# ProDocument_1_2024-06-25.net
KiCad netlist of a schematic drawn in EasyEDA Pro
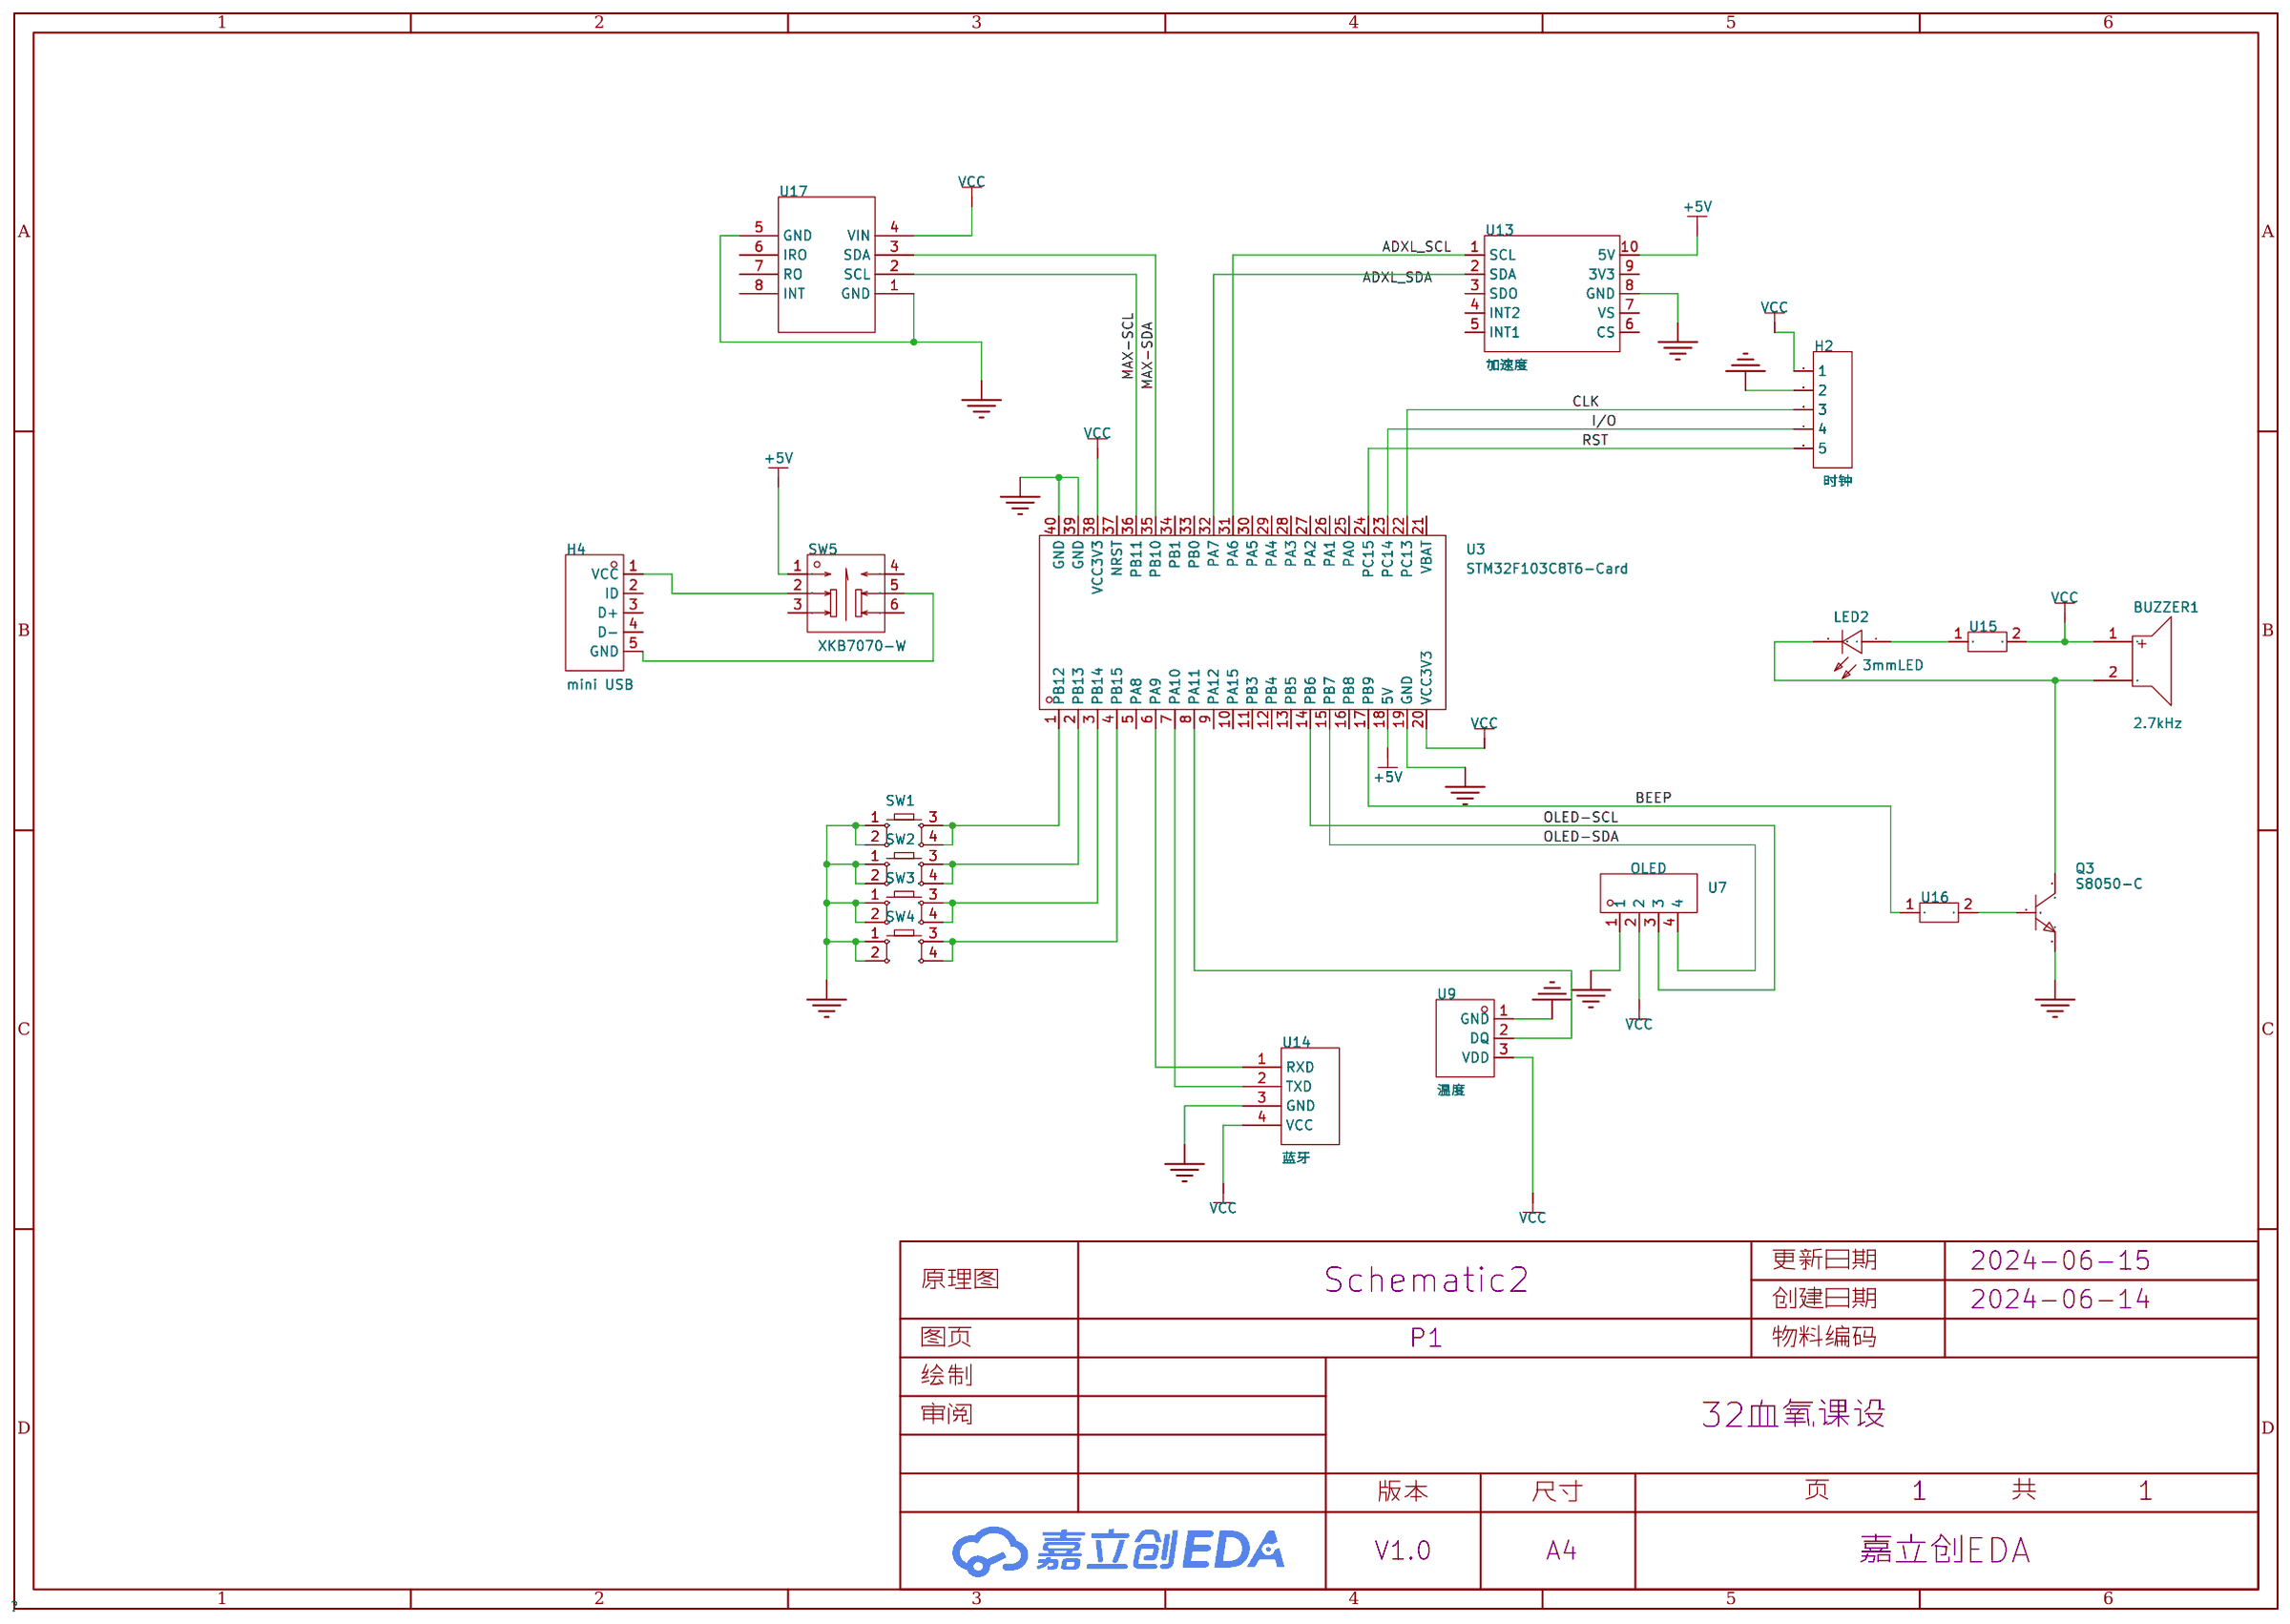
[diagram p0: schematic sheet]

(export (version "E")
  (design (tool "Eeschema 10.0.6"))
  (components
    (comp (ref "BUZZER1")
      (value "2.7kHz")
      (footprint "easyedapro:BUZ-TH_BD9.0-P4.00-D0.6-FD")
      (description "驱动方式:无源(外部驱动);构造类型:电磁式;频率:2.7kHz;声压(SPL):85dB@3V,10cm;")
      (fields (field (name "Manufacturer Part") "QMB-09B-03") (field (name "Manufacturer") "华能"))
      (libsource (lib "easyedapro") (part "QMB-09B-03"))
    )
    (comp (ref "H2")
      (value "时钟")
      (footprint "easyedapro:HDR-TH_5P-P2.54-V-F")
      (libsource (lib "easyedapro") (part "Header-Female-2.54_1x5"))
    )
    (comp (ref "H4") (value "mini USB") (libsource (lib "easyedapro") (part "mini USB")))
    (comp (ref "LED2")
      (value "3mmLED")
      (footprint "easyedapro:LED-TH_BD3.8-P2.54-FD")
      (fields
        (field (name "Manufacturer Part") "204-10SDRD/S530-A3-L")
        (field (name "Manufacturer") "EVERLIGHT(亿光)")
      )
      (libsource (lib "easyedapro") (part "3mmLED"))
    )
    (comp (ref "Q3")
      (value "S8050-C")
      (footprint "easyedapro:TO-92-3_L4.9-W3.7-P1.27-R")
      (description "晶体管类型:NPN;集电极电流(Ic):800mA;集射极击穿电压(Vceo):25V;功率(Pd):625mW;直流电流增益(hFE@Ic,Vce):120@100mA,1V;")
      (fields (field (name "Manufacturer") "BLUE ROCKET(蓝箭)"))
      (libsource (lib "easyedapro") (part "S8050-C"))
    )
    (comp (ref "SW1")
      (value "~")
      (footprint "easyedapro:SW-SMD_4P-L6.0-W6.0-P4.50-LS9.0-2")
      (libsource (lib "easyedapro") (part "轻触按键"))
    )
    (comp (ref "SW2")
      (value "~")
      (footprint "easyedapro:SW-SMD_4P-L6.0-W6.0-P4.50-LS9.0-2")
      (libsource (lib "easyedapro") (part "轻触按键"))
    )
    (comp (ref "SW3")
      (value "~")
      (footprint "easyedapro:SW-SMD_4P-L6.0-W6.0-P4.50-LS9.0-2")
      (libsource (lib "easyedapro") (part "轻触按键"))
    )
    (comp (ref "SW4")
      (value "~")
      (footprint "easyedapro:SW-SMD_4P-L6.0-W6.0-P4.50-LS9.0-2")
      (libsource (lib "easyedapro") (part "轻触按键"))
    )
    (comp (ref "SW5")
      (value "XKB7070-W")
      (footprint "easyedapro:SW-TH_6P-L7.2-W7.2-P2.00-LS5.0")
      (description "电路结构:-;自锁/无锁:无锁;安装方式:直插;触点电流:100mA;额定电压 (AC):250V;额定电压 (DC):30V;带灯:不带;作用力:160gf;机械寿命:1万次;")
      (fields (field (name "Manufacturer") "XKB Connectivity(中国星坤)"))
      (libsource (lib "easyedapro") (part "XKB7070-W"))
    )
    (comp (ref "U3")
      (value "STM32F103C8T6-Card")
      (footprint "easyedapro:CONN-TH_L53.3-W22.9_STM32F103C8T6-CARD")
      (libsource (lib "easyedapro") (part "STM32F103C8T6-CARD"))
    )
    (comp (ref "U7")
      (value "OLED")
      (footprint "easyedapro:OLED-TH12864")
      (libsource (lib "easyedapro") (part "1.3寸OLED显示屏12864"))
    )
    (comp (ref "U9")
      (value "温度")
      (footprint "easyedapro:TO-92-3_L4.9-W3.7-P1.27-L")
      (description "温度范围:-55°C~+125°C;精度:±0.4°C;接口类型:-;")
      (fields (field (name "Manufacturer Part") "DS18B20") (field (name "Manufacturer") "UMW(友台半导体)"))
      (libsource (lib "easyedapro") (part "DS18B20"))
    )
    (comp (ref "U13")
      (value "加速度")
      (footprint "easyedapro:HDR-TH_2x5P-P2.54-V-F-R2-C5-S2.54")
      (libsource (lib "easyedapro") (part "ADXL345"))
    )
    (comp (ref "U14")
      (value "蓝牙")
      (footprint "easyedapro:BT04-A")
      (libsource (lib "easyedapro") (part "BT04-A"))
    )
    (comp (ref "U15")
      (value "~")
      (footprint "easyedapro:R_AXIAL-0.3")
      (libsource (lib "easyedapro") (part "直插电阻"))
    )
    (comp (ref "U16")
      (value "~")
      (footprint "easyedapro:R_AXIAL-0.3")
      (libsource (lib "easyedapro") (part "直插电阻"))
    )
    (comp (ref "U17") (value "~") (libsource (lib "easyedapro") (part "MAX30102")))
  )
  (nets
    (net (code "1") (name "+5V") (class "Default")
      (node (ref "SW5") (pin "1") (pinfunction "1_1") (pintype "unspecified"))
      (node (ref "U13") (pin "10") (pinfunction "5V_10") (pintype "input"))
      (node (ref "U3") (pin "18") (pinfunction "5V_18") (pintype "unspecified"))
    )
    (net (code "2") (name "/ADXL_SCL") (class "Default")
      (node (ref "U13") (pin "1") (pinfunction "SCL_1") (pintype "input"))
      (node (ref "U3") (pin "31") (pinfunction "PA6_31") (pintype "unspecified"))
    )
    (net (code "3") (name "/ADXL_SDA") (class "Default")
      (node (ref "U13") (pin "2") (pinfunction "SDA_2") (pintype "input"))
      (node (ref "U3") (pin "32") (pinfunction "PA7_32") (pintype "unspecified"))
    )
    (net (code "4") (name "/BEEP") (class "Default")
      (node (ref "U16") (pin "1") (pinfunction "1_1") (pintype "input"))
      (node (ref "U3") (pin "17") (pinfunction "PB9_17") (pintype "unspecified"))
    )
    (net (code "5") (name "/CLK") (class "Default")
      (node (ref "H2") (pin "3") (pinfunction "3_3") (pintype "input"))
      (node (ref "U3") (pin "22") (pinfunction "PC13_22") (pintype "unspecified"))
    )
    (net (code "6") (name "/I{slash}O") (class "Default")
      (node (ref "H2") (pin "4") (pinfunction "4_4") (pintype "input"))
      (node (ref "U3") (pin "23") (pinfunction "PC14_23") (pintype "unspecified"))
    )
    (net (code "7") (name "/MAX-SCL") (class "Default")
      (node (ref "U17") (pin "2") (pinfunction "SCL_2") (pintype "input"))
      (node (ref "U3") (pin "36") (pinfunction "PB11_36") (pintype "unspecified"))
    )
    (net (code "8") (name "/MAX-SDA") (class "Default")
      (node (ref "U17") (pin "3") (pinfunction "SDA_3") (pintype "input"))
      (node (ref "U3") (pin "35") (pinfunction "PB10_35") (pintype "unspecified"))
    )
    (net (code "9") (name "/OLED-SCL") (class "Default")
      (node (ref "U3") (pin "14") (pinfunction "PB6_14") (pintype "unspecified"))
      (node (ref "U7") (pin "3") (pinfunction "3_3") (pintype "unspecified"))
    )
    (net (code "10") (name "/OLED-SDA") (class "Default")
      (node (ref "U3") (pin "15") (pinfunction "PB7_15") (pintype "unspecified"))
      (node (ref "U7") (pin "4") (pinfunction "4_4") (pintype "unspecified"))
    )
    (net (code "11") (name "/RST") (class "Default")
      (node (ref "H2") (pin "5") (pinfunction "5_5") (pintype "input"))
      (node (ref "U3") (pin "24") (pinfunction "PC15_24") (pintype "unspecified"))
    )
    (net (code "12") (name "GND") (class "Default")
      (node (ref "H2") (pin "2") (pinfunction "2_2") (pintype "input"))
      (node (ref "Q3") (pin "3") (pinfunction "E_3") (pintype "unspecified"))
      (node (ref "SW1") (pin "1") (pinfunction "1_1") (pintype "input"))
      (node (ref "SW1") (pin "2") (pinfunction "2_2") (pintype "input"))
      (node (ref "SW2") (pin "1") (pinfunction "1_1") (pintype "input"))
      (node (ref "SW2") (pin "2") (pinfunction "2_2") (pintype "input"))
      (node (ref "SW3") (pin "1") (pinfunction "1_1") (pintype "input"))
      (node (ref "SW3") (pin "2") (pinfunction "2_2") (pintype "input"))
      (node (ref "SW4") (pin "1") (pinfunction "1_1") (pintype "input"))
      (node (ref "SW4") (pin "2") (pinfunction "2_2") (pintype "input"))
      (node (ref "U13") (pin "8") (pinfunction "GND_8") (pintype "input"))
      (node (ref "U14") (pin "3") (pinfunction "GND_3") (pintype "input"))
      (node (ref "U17") (pin "1") (pinfunction "GND_1") (pintype "input"))
      (node (ref "U17") (pin "5") (pinfunction "GND_5") (pintype "input"))
      (node (ref "U3") (pin "19") (pinfunction "GND_19") (pintype "unspecified"))
      (node (ref "U3") (pin "39") (pinfunction "GND_39") (pintype "unspecified"))
      (node (ref "U3") (pin "40") (pinfunction "GND_40") (pintype "unspecified"))
      (node (ref "U7") (pin "1") (pinfunction "1_1") (pintype "unspecified"))
      (node (ref "U9") (pin "1") (pinfunction "GND_1") (pintype "unspecified"))
    )
    (net (code "13") (name "Net-(H4-GND)") (class "Default")
      (node (ref "H4") (pin "5") (pinfunction "GND_5") (pintype "input"))
      (node (ref "SW5") (pin "5") (pinfunction "5_5") (pintype "unspecified"))
    )
    (net (code "14") (name "Net-(H4-VCC)") (class "Default")
      (node (ref "H4") (pin "1") (pinfunction "VCC_1") (pintype "input"))
      (node (ref "SW5") (pin "2") (pinfunction "2_2") (pintype "unspecified"))
    )
    (net (code "15") (name "Net-(LED2-A)") (class "Default")
      (node (ref "LED2") (pin "1") (pinfunction "A_1") (pintype "unspecified"))
      (node (ref "U15") (pin "1") (pinfunction "1_1") (pintype "input"))
    )
    (net (code "16") (name "Net-(LED2-C)") (class "Default")
      (node (ref "BUZZER1") (pin "2") (pinfunction "2_2") (pintype "unspecified"))
      (node (ref "LED2") (pin "2") (pinfunction "C_2") (pintype "unspecified"))
      (node (ref "Q3") (pin "1") (pinfunction "C_1") (pintype "unspecified"))
    )
    (net (code "17") (name "Net-(Q3-B)") (class "Default")
      (node (ref "Q3") (pin "2") (pinfunction "B_2") (pintype "unspecified"))
      (node (ref "U16") (pin "2") (pinfunction "2_2") (pintype "input"))
    )
    (net (code "18") (name "Net-(U3-PA11)") (class "Default")
      (node (ref "U3") (pin "8") (pinfunction "PA11_8") (pintype "unspecified"))
      (node (ref "U9") (pin "2") (pinfunction "DQ_2") (pintype "unspecified"))
    )
    (net (code "19") (name "Net-(U3-PB12)") (class "Default")
      (node (ref "SW1") (pin "3") (pinfunction "3_3") (pintype "input"))
      (node (ref "SW1") (pin "4") (pinfunction "4_4") (pintype "input"))
      (node (ref "U3") (pin "1") (pinfunction "PB12_1") (pintype "unspecified"))
    )
    (net (code "20") (name "Net-(U3-PB13)") (class "Default")
      (node (ref "SW2") (pin "3") (pinfunction "3_3") (pintype "input"))
      (node (ref "SW2") (pin "4") (pinfunction "4_4") (pintype "input"))
      (node (ref "U3") (pin "2") (pinfunction "PB13_2") (pintype "unspecified"))
    )
    (net (code "21") (name "Net-(U3-PB14)") (class "Default")
      (node (ref "SW3") (pin "3") (pinfunction "3_3") (pintype "input"))
      (node (ref "SW3") (pin "4") (pinfunction "4_4") (pintype "input"))
      (node (ref "U3") (pin "3") (pinfunction "PB14_3") (pintype "unspecified"))
    )
    (net (code "22") (name "Net-(U3-PB15)") (class "Default")
      (node (ref "SW4") (pin "3") (pinfunction "3_3") (pintype "input"))
      (node (ref "SW4") (pin "4") (pinfunction "4_4") (pintype "input"))
      (node (ref "U3") (pin "4") (pinfunction "PB15_4") (pintype "unspecified"))
    )
    (net (code "23") (name "Net-(U14-RXD)") (class "Default")
      (node (ref "U14") (pin "1") (pinfunction "RXD_1") (pintype "input"))
      (node (ref "U3") (pin "6") (pinfunction "PA9_6") (pintype "unspecified"))
    )
    (net (code "24") (name "Net-(U14-TXD)") (class "Default")
      (node (ref "U14") (pin "2") (pinfunction "TXD_2") (pintype "input"))
      (node (ref "U3") (pin "7") (pinfunction "PA10_7") (pintype "unspecified"))
    )
    (net (code "25") (name "VCC") (class "Default")
      (node (ref "BUZZER1") (pin "1") (pinfunction "1_1") (pintype "unspecified"))
      (node (ref "H2") (pin "1") (pinfunction "1_1") (pintype "input"))
      (node (ref "U14") (pin "4") (pinfunction "VCC_4") (pintype "input"))
      (node (ref "U15") (pin "2") (pinfunction "2_2") (pintype "input"))
      (node (ref "U17") (pin "4") (pinfunction "VIN_4") (pintype "input"))
      (node (ref "U3") (pin "20") (pinfunction "VCC3V3_20") (pintype "unspecified"))
      (node (ref "U3") (pin "38") (pinfunction "VCC3V3_38") (pintype "unspecified"))
      (node (ref "U7") (pin "2") (pinfunction "2_2") (pintype "unspecified"))
      (node (ref "U9") (pin "3") (pinfunction "VDD_3") (pintype "unspecified"))
    )
    (net (code "26") (name "unconnected-(H4-D+-Pad3)") (class "Default")
      (node (ref "H4") (pin "3") (pinfunction "D+_3") (pintype "input"))
    )
    (net (code "27") (name "unconnected-(H4-D--Pad4)") (class "Default")
      (node (ref "H4") (pin "4") (pinfunction "D-_4") (pintype "input"))
    )
    (net (code "28") (name "unconnected-(H4-ID-Pad2)") (class "Default")
      (node (ref "H4") (pin "2") (pinfunction "ID_2") (pintype "input"))
    )
    (net (code "29") (name "unconnected-(SW5-Pad3)") (class "Default")
      (node (ref "SW5") (pin "3") (pinfunction "3_3") (pintype "unspecified"))
    )
    (net (code "30") (name "unconnected-(SW5-Pad4)") (class "Default")
      (node (ref "SW5") (pin "4") (pinfunction "4_4") (pintype "unspecified"))
    )
    (net (code "31") (name "unconnected-(SW5-Pad6)") (class "Default")
      (node (ref "SW5") (pin "6") (pinfunction "6_6") (pintype "unspecified"))
    )
    (net (code "32") (name "unconnected-(U3-NRST-Pad37)") (class "Default")
      (node (ref "U3") (pin "37") (pinfunction "NRST_37") (pintype "unspecified"))
    )
    (net (code "33") (name "unconnected-(U3-PA0-Pad25)") (class "Default")
      (node (ref "U3") (pin "25") (pinfunction "PA0_25") (pintype "unspecified"))
    )
    (net (code "34") (name "unconnected-(U3-PA1-Pad26)") (class "Default")
      (node (ref "U3") (pin "26") (pinfunction "PA1_26") (pintype "unspecified"))
    )
    (net (code "35") (name "unconnected-(U3-PA2-Pad27)") (class "Default")
      (node (ref "U3") (pin "27") (pinfunction "PA2_27") (pintype "unspecified"))
    )
    (net (code "36") (name "unconnected-(U3-PA3-Pad28)") (class "Default")
      (node (ref "U3") (pin "28") (pinfunction "PA3_28") (pintype "unspecified"))
    )
    (net (code "37") (name "unconnected-(U3-PA4-Pad29)") (class "Default")
      (node (ref "U3") (pin "29") (pinfunction "PA4_29") (pintype "unspecified"))
    )
    (net (code "38") (name "unconnected-(U3-PA5-Pad30)") (class "Default")
      (node (ref "U3") (pin "30") (pinfunction "PA5_30") (pintype "unspecified"))
    )
    (net (code "39") (name "unconnected-(U3-PA8-Pad5)") (class "Default")
      (node (ref "U3") (pin "5") (pinfunction "PA8_5") (pintype "unspecified"))
    )
    (net (code "40") (name "unconnected-(U3-PA12-Pad9)") (class "Default")
      (node (ref "U3") (pin "9") (pinfunction "PA12_9") (pintype "unspecified"))
    )
    (net (code "41") (name "unconnected-(U3-PA15-Pad10)") (class "Default")
      (node (ref "U3") (pin "10") (pinfunction "PA15_10") (pintype "unspecified"))
    )
    (net (code "42") (name "unconnected-(U3-PB0-Pad33)") (class "Default")
      (node (ref "U3") (pin "33") (pinfunction "PB0_33") (pintype "unspecified"))
    )
    (net (code "43") (name "unconnected-(U3-PB1-Pad34)") (class "Default")
      (node (ref "U3") (pin "34") (pinfunction "PB1_34") (pintype "unspecified"))
    )
    (net (code "44") (name "unconnected-(U3-PB3-Pad11)") (class "Default")
      (node (ref "U3") (pin "11") (pinfunction "PB3_11") (pintype "unspecified"))
    )
    (net (code "45") (name "unconnected-(U3-PB4-Pad12)") (class "Default")
      (node (ref "U3") (pin "12") (pinfunction "PB4_12") (pintype "unspecified"))
    )
    (net (code "46") (name "unconnected-(U3-PB5-Pad13)") (class "Default")
      (node (ref "U3") (pin "13") (pinfunction "PB5_13") (pintype "unspecified"))
    )
    (net (code "47") (name "unconnected-(U3-PB8-Pad16)") (class "Default")
      (node (ref "U3") (pin "16") (pinfunction "PB8_16") (pintype "unspecified"))
    )
    (net (code "48") (name "unconnected-(U3-VBAT-Pad21)") (class "Default")
      (node (ref "U3") (pin "21") (pinfunction "VBAT_21") (pintype "unspecified"))
    )
    (net (code "49") (name "unconnected-(U13-3V3-Pad9)") (class "Default")
      (node (ref "U13") (pin "9") (pinfunction "3V3_9") (pintype "input"))
    )
    (net (code "50") (name "unconnected-(U13-CS-Pad6)") (class "Default")
      (node (ref "U13") (pin "6") (pinfunction "CS_6") (pintype "input"))
    )
    (net (code "51") (name "unconnected-(U13-INT1-Pad5)") (class "Default")
      (node (ref "U13") (pin "5") (pinfunction "INT1_5") (pintype "input"))
    )
    (net (code "52") (name "unconnected-(U13-INT2-Pad4)") (class "Default")
      (node (ref "U13") (pin "4") (pinfunction "INT2_4") (pintype "input"))
    )
    (net (code "53") (name "unconnected-(U13-SDO-Pad3)") (class "Default")
      (node (ref "U13") (pin "3") (pinfunction "SDO_3") (pintype "input"))
    )
    (net (code "54") (name "unconnected-(U13-VS-Pad7)") (class "Default")
      (node (ref "U13") (pin "7") (pinfunction "VS_7") (pintype "input"))
    )
    (net (code "55") (name "unconnected-(U17-INT-Pad8)") (class "Default")
      (node (ref "U17") (pin "8") (pinfunction "INT_8") (pintype "input"))
    )
    (net (code "56") (name "unconnected-(U17-IRO-Pad6)") (class "Default")
      (node (ref "U17") (pin "6") (pinfunction "IRO_6") (pintype "input"))
    )
    (net (code "57") (name "unconnected-(U17-RO-Pad7)") (class "Default")
      (node (ref "U17") (pin "7") (pinfunction "RO_7") (pintype "input"))
    )
  )
)
